# connector.net
KiCad netlist of a schematic drawn in Altium Designer
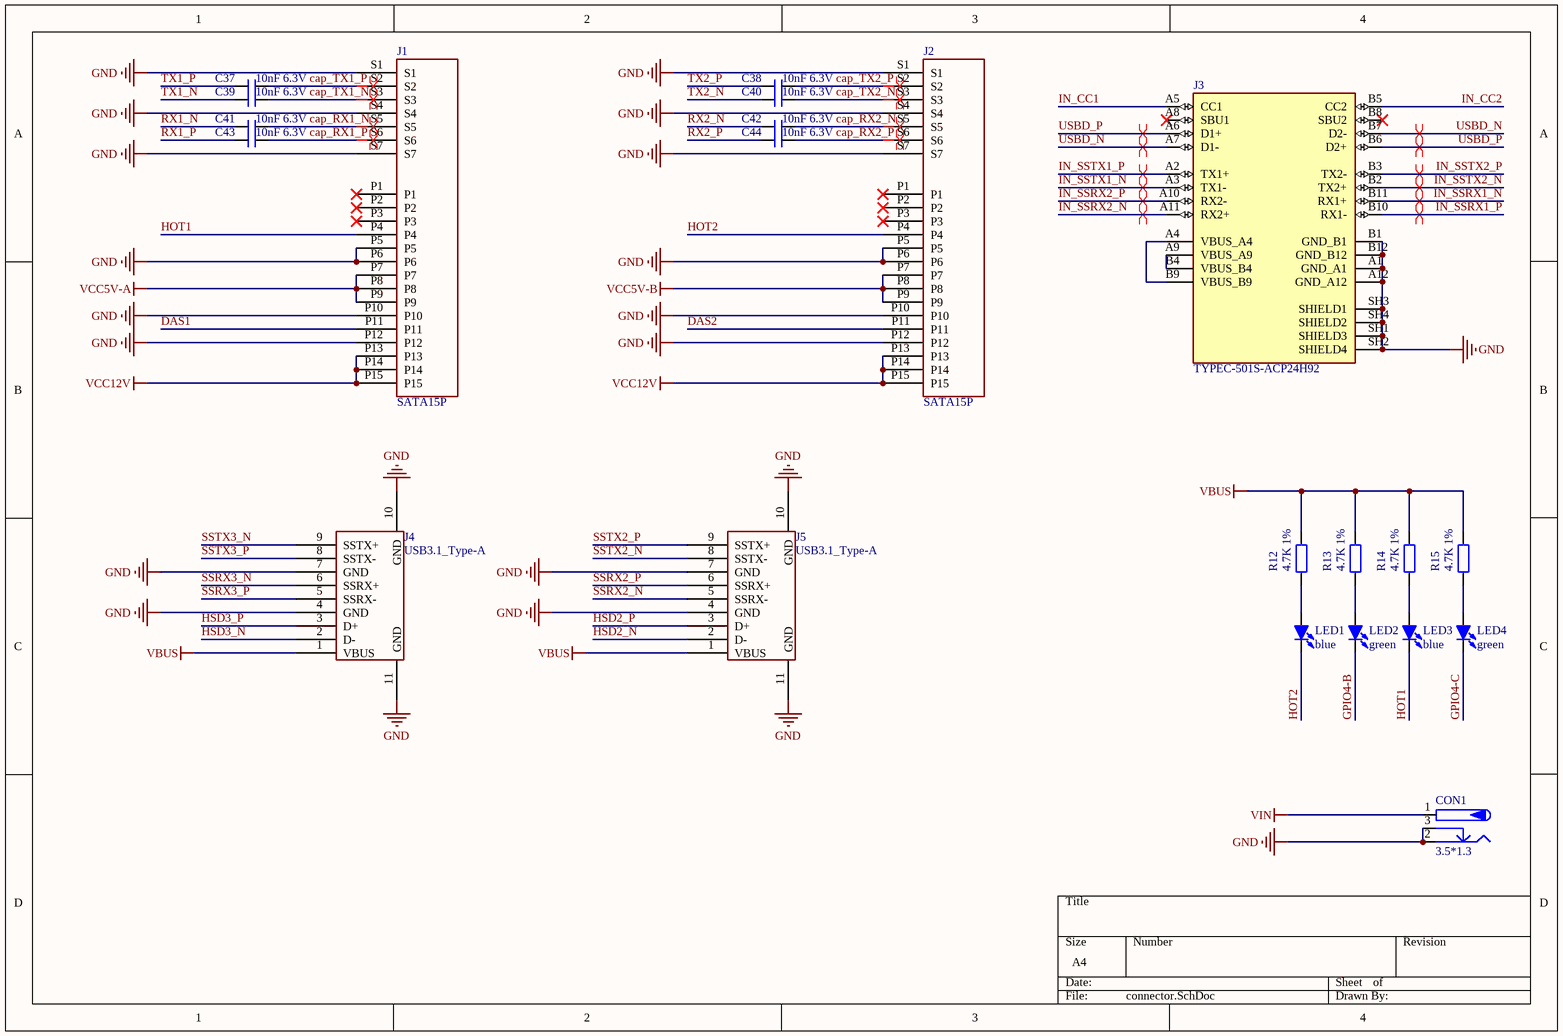
[diagram p0: connector.SchDoc]

(export (version "E")
  (design (tool "Eeschema 10.0.6"))
  (components
    (comp (ref "C37")
      (value "10nF 6.3V")
      (footprint "C0402_L")
      (description "无极性贴片电容")
      (fields (field (name "版权归属") "源创客"))
      (libsource (lib "Capacitor") (part "C"))
    )
    (comp (ref "C38")
      (value "10nF 6.3V")
      (footprint "C0402_L")
      (description "无极性贴片电容")
      (fields (field (name "版权归属") "源创客"))
      (libsource (lib "Capacitor") (part "C"))
    )
    (comp (ref "C39")
      (value "10nF 6.3V")
      (footprint "C0402_L")
      (description "无极性贴片电容")
      (fields (field (name "版权归属") "源创客"))
      (libsource (lib "Capacitor") (part "C"))
    )
    (comp (ref "C40")
      (value "10nF 6.3V")
      (footprint "C0402_L")
      (description "无极性贴片电容")
      (fields (field (name "版权归属") "源创客"))
      (libsource (lib "Capacitor") (part "C"))
    )
    (comp (ref "C41")
      (value "10nF 6.3V")
      (footprint "C0402_L")
      (description "无极性贴片电容")
      (fields (field (name "版权归属") "源创客"))
      (libsource (lib "Capacitor") (part "C"))
    )
    (comp (ref "C42")
      (value "10nF 6.3V")
      (footprint "C0402_L")
      (description "无极性贴片电容")
      (fields (field (name "版权归属") "源创客"))
      (libsource (lib "Capacitor") (part "C"))
    )
    (comp (ref "C43")
      (value "10nF 6.3V")
      (footprint "C0402_L")
      (description "无极性贴片电容")
      (fields (field (name "版权归属") "源创客"))
      (libsource (lib "Capacitor") (part "C"))
    )
    (comp (ref "C44")
      (value "10nF 6.3V")
      (footprint "C0402_L")
      (description "无极性贴片电容")
      (fields (field (name "版权归属") "源创客"))
      (libsource (lib "Capacitor") (part "C"))
    )
    (comp (ref "CON1")
      (value "3.5*1.3")
      (footprint "DC-012G-2.5")
      (description "低压电源接口")
      (fields (field (name "版权归属") "源创客"))
      (libsource (lib "Connector-PWR") (part "P-DC"))
    )
    (comp (ref "J1")
      (value "SATA15P")
      (footprint "SATA 15P 贴片")
      (libsource (lib "Connector-SATA&SAS") (part "SATA15P"))
    )
    (comp (ref "J2")
      (value "SATA15P")
      (footprint "SATA 15P 贴片")
      (libsource (lib "Connector-SATA&SAS") (part "SATA15P"))
    )
    (comp (ref "J3")
      (value "TYPEC-501S-ACP24H92")
      (footprint "TypeC 24p 直立")
      (fields (field (name "MF") "Molex") (field (name "MP") "1054500101"))
      (libsource (lib "Connector-USB") (part "Typec 24p"))
    )
    (comp (ref "J4")
      (value "USB3.1_Type-A")
      (footprint "USB3.1_Type-A 立式直插")
      (description "USB接口")
      (libsource (lib "Connector-USB") (part "USB3.1_Type-A"))
    )
    (comp (ref "J5")
      (value "USB3.1_Type-A")
      (footprint "USB3.1_Type-A 立式直插")
      (description "USB接口")
      (libsource (lib "Connector-USB") (part "USB3.1_Type-A"))
    )
    (comp (ref "LED1")
      (value "blue")
      (footprint "LED 0805B")
      (description "插件LED")
      (fields (field (name "版权归属") "源创客"))
      (libsource (lib "LED") (part "LED-3MM"))
    )
    (comp (ref "LED2")
      (value "green")
      (footprint "LED 0805G")
      (description "插件LED")
      (fields (field (name "版权归属") "源创客"))
      (libsource (lib "LED") (part "LED-3MM"))
    )
    (comp (ref "LED3")
      (value "blue")
      (footprint "LED 0805B")
      (description "插件LED")
      (fields (field (name "版权归属") "源创客"))
      (libsource (lib "LED") (part "LED-3MM"))
    )
    (comp (ref "LED4")
      (value "green")
      (footprint "LED 0805G")
      (description "插件LED")
      (fields (field (name "版权归属") "源创客"))
      (libsource (lib "LED") (part "LED-3MM"))
    )
    (comp (ref "R12")
      (value "4.7K 1%")
      (footprint "R0402_L")
      (description "贴片电阻")
      (fields (field (name "版权归属") "源创客"))
      (libsource (lib "Resistor") (part "R"))
    )
    (comp (ref "R13")
      (value "4.7K 1%")
      (footprint "R0402_L")
      (description "贴片电阻")
      (fields (field (name "版权归属") "源创客"))
      (libsource (lib "Resistor") (part "R"))
    )
    (comp (ref "R14")
      (value "4.7K 1%")
      (footprint "R0402_L")
      (description "贴片电阻")
      (fields (field (name "版权归属") "源创客"))
      (libsource (lib "Resistor") (part "R"))
    )
    (comp (ref "R15")
      (value "4.7K 1%")
      (footprint "R0402_L")
      (description "贴片电阻")
      (fields (field (name "版权归属") "源创客"))
      (libsource (lib "Resistor") (part "R"))
    )
  )
  (nets
    (net (code "1") (name "/DAS1") (class "Default")
      (node (ref "J1") (pin "P11") (pinfunction "P11_P11") (pintype "passive"))
    )
    (net (code "2") (name "/DAS2") (class "Default")
      (node (ref "J2") (pin "P11") (pinfunction "P11_P11") (pintype "passive"))
    )
    (net (code "3") (name "/GPIO4-B") (class "Default")
      (node (ref "LED2") (pin "2") (pinfunction "K_2") (pintype "passive"))
    )
    (net (code "4") (name "/GPIO4-C") (class "Default")
      (node (ref "LED4") (pin "2") (pinfunction "K_2") (pintype "passive"))
    )
    (net (code "5") (name "/HOT1") (class "Default")
      (node (ref "J1") (pin "P4") (pinfunction "P4_P4") (pintype "passive"))
      (node (ref "LED3") (pin "2") (pinfunction "K_2") (pintype "passive"))
    )
    (net (code "6") (name "/HOT2") (class "Default")
      (node (ref "J2") (pin "P4") (pinfunction "P4_P4") (pintype "passive"))
      (node (ref "LED1") (pin "2") (pinfunction "K_2") (pintype "passive"))
    )
    (net (code "7") (name "/HSD2_N") (class "Default")
      (node (ref "J5") (pin "2") (pinfunction "D-_2") (pintype "passive"))
    )
    (net (code "8") (name "/HSD2_P") (class "Default")
      (node (ref "J5") (pin "3") (pinfunction "D+_3") (pintype "passive"))
    )
    (net (code "9") (name "/HSD3_N") (class "Default")
      (node (ref "J4") (pin "2") (pinfunction "D-_2") (pintype "passive"))
    )
    (net (code "10") (name "/HSD3_P") (class "Default")
      (node (ref "J4") (pin "3") (pinfunction "D+_3") (pintype "passive"))
    )
    (net (code "11") (name "/IN_CC1") (class "Default")
      (node (ref "J3") (pin "A5") (pinfunction "CC1_A5") (pintype "bidirectional"))
    )
    (net (code "12") (name "/IN_CC2") (class "Default")
      (node (ref "J3") (pin "B5") (pinfunction "CC2_B5") (pintype "bidirectional"))
    )
    (net (code "13") (name "/IN_SSRX1_N") (class "Default")
      (node (ref "J3") (pin "B11") (pinfunction "RX1+_B11") (pintype "bidirectional"))
    )
    (net (code "14") (name "/IN_SSRX1_P") (class "Default")
      (node (ref "J3") (pin "B10") (pinfunction "RX1-_B10") (pintype "bidirectional"))
    )
    (net (code "15") (name "/IN_SSRX2_N") (class "Default")
      (node (ref "J3") (pin "A11") (pinfunction "RX2+_A11") (pintype "bidirectional"))
    )
    (net (code "16") (name "/IN_SSRX2_P") (class "Default")
      (node (ref "J3") (pin "A10") (pinfunction "RX2-_A10") (pintype "bidirectional"))
    )
    (net (code "17") (name "/IN_SSTX1_N") (class "Default")
      (node (ref "J3") (pin "A3") (pinfunction "TX1-_A3") (pintype "bidirectional"))
    )
    (net (code "18") (name "/IN_SSTX1_P") (class "Default")
      (node (ref "J3") (pin "A2") (pinfunction "TX1+_A2") (pintype "bidirectional"))
    )
    (net (code "19") (name "/IN_SSTX2_N") (class "Default")
      (node (ref "J3") (pin "B2") (pinfunction "TX2+_B2") (pintype "bidirectional"))
    )
    (net (code "20") (name "/IN_SSTX2_P") (class "Default")
      (node (ref "J3") (pin "B3") (pinfunction "TX2-_B3") (pintype "bidirectional"))
    )
    (net (code "21") (name "/RX1_N") (class "Default")
      (node (ref "C41") (pin "2") (pinfunction "2_2") (pintype "passive"))
    )
    (net (code "22") (name "/RX1_P") (class "Default")
      (node (ref "C43") (pin "2") (pinfunction "2_2") (pintype "passive"))
    )
    (net (code "23") (name "/RX2_N") (class "Default")
      (node (ref "C42") (pin "2") (pinfunction "2_2") (pintype "passive"))
    )
    (net (code "24") (name "/RX2_P") (class "Default")
      (node (ref "C44") (pin "2") (pinfunction "2_2") (pintype "passive"))
    )
    (net (code "25") (name "/SSRX2_N") (class "Default")
      (node (ref "J5") (pin "5") (pinfunction "SSRX-_5") (pintype "passive"))
    )
    (net (code "26") (name "/SSRX2_P") (class "Default")
      (node (ref "J5") (pin "6") (pinfunction "SSRX+_6") (pintype "passive"))
    )
    (net (code "27") (name "/SSRX3_N") (class "Default")
      (node (ref "J4") (pin "6") (pinfunction "SSRX+_6") (pintype "passive"))
    )
    (net (code "28") (name "/SSRX3_P") (class "Default")
      (node (ref "J4") (pin "5") (pinfunction "SSRX-_5") (pintype "passive"))
    )
    (net (code "29") (name "/SSTX2_N") (class "Default")
      (node (ref "J5") (pin "8") (pinfunction "SSTX-_8") (pintype "passive"))
    )
    (net (code "30") (name "/SSTX2_P") (class "Default")
      (node (ref "J5") (pin "9") (pinfunction "SSTX+_9") (pintype "passive"))
    )
    (net (code "31") (name "/SSTX3_N") (class "Default")
      (node (ref "J4") (pin "9") (pinfunction "SSTX+_9") (pintype "passive"))
    )
    (net (code "32") (name "/SSTX3_P") (class "Default")
      (node (ref "J4") (pin "8") (pinfunction "SSTX-_8") (pintype "passive"))
    )
    (net (code "33") (name "/TX1_N") (class "Default")
      (node (ref "C39") (pin "2") (pinfunction "2_2") (pintype "passive"))
    )
    (net (code "34") (name "/TX1_P") (class "Default")
      (node (ref "C37") (pin "2") (pinfunction "2_2") (pintype "passive"))
    )
    (net (code "35") (name "/TX2_N") (class "Default")
      (node (ref "C40") (pin "2") (pinfunction "2_2") (pintype "passive"))
    )
    (net (code "36") (name "/TX2_P") (class "Default")
      (node (ref "C38") (pin "2") (pinfunction "2_2") (pintype "passive"))
    )
    (net (code "37") (name "/USBD_N") (class "Default")
      (node (ref "J3") (pin "A7") (pinfunction "D1-_A7") (pintype "bidirectional"))
      (node (ref "J3") (pin "B7") (pinfunction "D2-_B7") (pintype "bidirectional"))
    )
    (net (code "38") (name "/USBD_P") (class "Default")
      (node (ref "J3") (pin "A6") (pinfunction "D1+_A6") (pintype "bidirectional"))
      (node (ref "J3") (pin "B6") (pinfunction "D2+_B6") (pintype "bidirectional"))
    )
    (net (code "39") (name "/cap_RX1_N") (class "Default")
      (node (ref "C41") (pin "1") (pinfunction "1_1") (pintype "passive"))
      (node (ref "J1") (pin "S5") (pinfunction "S5_S5") (pintype "passive"))
    )
    (net (code "40") (name "/cap_RX1_P") (class "Default")
      (node (ref "C43") (pin "1") (pinfunction "1_1") (pintype "passive"))
      (node (ref "J1") (pin "S6") (pinfunction "S6_S6") (pintype "passive"))
    )
    (net (code "41") (name "/cap_RX2_N") (class "Default")
      (node (ref "C42") (pin "1") (pinfunction "1_1") (pintype "passive"))
      (node (ref "J2") (pin "S5") (pinfunction "S5_S5") (pintype "passive"))
    )
    (net (code "42") (name "/cap_RX2_P") (class "Default")
      (node (ref "C44") (pin "1") (pinfunction "1_1") (pintype "passive"))
      (node (ref "J2") (pin "S6") (pinfunction "S6_S6") (pintype "passive"))
    )
    (net (code "43") (name "/cap_TX1_N") (class "Default")
      (node (ref "C39") (pin "1") (pinfunction "1_1") (pintype "passive"))
      (node (ref "J1") (pin "S3") (pinfunction "S3_S3") (pintype "passive"))
    )
    (net (code "44") (name "/cap_TX1_P") (class "Default")
      (node (ref "C37") (pin "1") (pinfunction "1_1") (pintype "passive"))
      (node (ref "J1") (pin "S2") (pinfunction "S2_S2") (pintype "passive"))
    )
    (net (code "45") (name "/cap_TX2_N") (class "Default")
      (node (ref "C40") (pin "1") (pinfunction "1_1") (pintype "passive"))
      (node (ref "J2") (pin "S3") (pinfunction "S3_S3") (pintype "passive"))
    )
    (net (code "46") (name "/cap_TX2_P") (class "Default")
      (node (ref "C38") (pin "1") (pinfunction "1_1") (pintype "passive"))
      (node (ref "J2") (pin "S2") (pinfunction "S2_S2") (pintype "passive"))
    )
    (net (code "47") (name "GND") (class "Default")
      (node (ref "CON1") (pin "2") (pintype "power_in"))
      (node (ref "CON1") (pin "3") (pintype "power_in"))
      (node (ref "J1") (pin "P10") (pinfunction "P10_P10") (pintype "passive"))
      (node (ref "J1") (pin "P12") (pinfunction "P12_P12") (pintype "passive"))
      (node (ref "J1") (pin "P5") (pinfunction "P5_P5") (pintype "passive"))
      (node (ref "J1") (pin "P6") (pinfunction "P6_P6") (pintype "passive"))
      (node (ref "J1") (pin "S1") (pinfunction "S1_S1") (pintype "passive"))
      (node (ref "J1") (pin "S4") (pinfunction "S4_S4") (pintype "passive"))
      (node (ref "J1") (pin "S7") (pinfunction "S7_S7") (pintype "passive"))
      (node (ref "J2") (pin "P10") (pinfunction "P10_P10") (pintype "passive"))
      (node (ref "J2") (pin "P12") (pinfunction "P12_P12") (pintype "passive"))
      (node (ref "J2") (pin "P5") (pinfunction "P5_P5") (pintype "passive"))
      (node (ref "J2") (pin "P6") (pinfunction "P6_P6") (pintype "passive"))
      (node (ref "J2") (pin "S1") (pinfunction "S1_S1") (pintype "passive"))
      (node (ref "J2") (pin "S4") (pinfunction "S4_S4") (pintype "passive"))
      (node (ref "J2") (pin "S7") (pinfunction "S7_S7") (pintype "passive"))
      (node (ref "J3") (pin "A1") (pinfunction "GND_A1_A1") (pintype "power_in"))
      (node (ref "J3") (pin "A12") (pinfunction "GND_A12_A12") (pintype "power_in"))
      (node (ref "J3") (pin "B1") (pinfunction "GND_B1_B1") (pintype "power_in"))
      (node (ref "J3") (pin "B12") (pinfunction "GND_B12_B12") (pintype "power_in"))
      (node (ref "J3") (pin "SH1") (pinfunction "SHIELD3_SH1") (pintype "passive"))
      (node (ref "J3") (pin "SH2") (pinfunction "SHIELD4_SH2") (pintype "passive"))
      (node (ref "J3") (pin "SH3") (pinfunction "SHIELD1_SH3") (pintype "passive"))
      (node (ref "J3") (pin "SH4") (pinfunction "SHIELD2_SH4") (pintype "passive"))
      (node (ref "J4") (pin "10") (pinfunction "GND_10") (pintype "passive"))
      (node (ref "J4") (pin "11") (pinfunction "GND_11") (pintype "passive"))
      (node (ref "J4") (pin "4") (pinfunction "GND_4") (pintype "passive"))
      (node (ref "J4") (pin "7") (pinfunction "GND_7") (pintype "passive"))
      (node (ref "J5") (pin "10") (pinfunction "GND_10") (pintype "passive"))
      (node (ref "J5") (pin "11") (pinfunction "GND_11") (pintype "passive"))
      (node (ref "J5") (pin "4") (pinfunction "GND_4") (pintype "passive"))
      (node (ref "J5") (pin "7") (pinfunction "GND_7") (pintype "passive"))
    )
    (net (code "48") (name "Net-(J3-VBUS_A4)") (class "Default")
      (node (ref "J3") (pin "A4") (pinfunction "VBUS_A4_A4") (pintype "power_in"))
      (node (ref "J3") (pin "B9") (pinfunction "VBUS_B9_B9") (pintype "power_in"))
    )
    (net (code "49") (name "Net-(J3-VBUS_A9)") (class "Default")
      (node (ref "J3") (pin "A9") (pinfunction "VBUS_A9_A9") (pintype "power_in"))
      (node (ref "J3") (pin "B4") (pinfunction "VBUS_B4_B4") (pintype "power_in"))
    )
    (net (code "50") (name "Net-(LED1-A)") (class "Default")
      (node (ref "LED1") (pin "1") (pinfunction "A_1") (pintype "passive"))
      (node (ref "R12") (pin "2") (pinfunction "2_2") (pintype "passive"))
    )
    (net (code "51") (name "Net-(LED2-A)") (class "Default")
      (node (ref "LED2") (pin "1") (pinfunction "A_1") (pintype "passive"))
      (node (ref "R13") (pin "2") (pinfunction "2_2") (pintype "passive"))
    )
    (net (code "52") (name "Net-(LED3-A)") (class "Default")
      (node (ref "LED3") (pin "1") (pinfunction "A_1") (pintype "passive"))
      (node (ref "R14") (pin "2") (pinfunction "2_2") (pintype "passive"))
    )
    (net (code "53") (name "Net-(LED4-A)") (class "Default")
      (node (ref "LED4") (pin "1") (pinfunction "A_1") (pintype "passive"))
      (node (ref "R15") (pin "2") (pinfunction "2_2") (pintype "passive"))
    )
    (net (code "54") (name "VBUS") (class "Default")
      (node (ref "J4") (pin "1") (pinfunction "VBUS_1") (pintype "passive"))
      (node (ref "J5") (pin "1") (pinfunction "VBUS_1") (pintype "passive"))
      (node (ref "R12") (pin "1") (pinfunction "1_1") (pintype "passive"))
      (node (ref "R13") (pin "1") (pinfunction "1_1") (pintype "passive"))
      (node (ref "R14") (pin "1") (pinfunction "1_1") (pintype "passive"))
      (node (ref "R15") (pin "1") (pinfunction "1_1") (pintype "passive"))
    )
    (net (code "55") (name "VCC5V-A") (class "Default")
      (node (ref "J1") (pin "P7") (pinfunction "P7_P7") (pintype "passive"))
      (node (ref "J1") (pin "P8") (pinfunction "P8_P8") (pintype "passive"))
      (node (ref "J1") (pin "P9") (pinfunction "P9_P9") (pintype "passive"))
    )
    (net (code "56") (name "VCC5V-B") (class "Default")
      (node (ref "J2") (pin "P7") (pinfunction "P7_P7") (pintype "passive"))
      (node (ref "J2") (pin "P8") (pinfunction "P8_P8") (pintype "passive"))
      (node (ref "J2") (pin "P9") (pinfunction "P9_P9") (pintype "passive"))
    )
    (net (code "57") (name "VCC12V") (class "Default")
      (node (ref "J1") (pin "P13") (pinfunction "P13_P13") (pintype "passive"))
      (node (ref "J1") (pin "P14") (pinfunction "P14_P14") (pintype "passive"))
      (node (ref "J1") (pin "P15") (pinfunction "P15_P15") (pintype "passive"))
      (node (ref "J2") (pin "P13") (pinfunction "P13_P13") (pintype "passive"))
      (node (ref "J2") (pin "P14") (pinfunction "P14_P14") (pintype "passive"))
      (node (ref "J2") (pin "P15") (pinfunction "P15_P15") (pintype "passive"))
    )
    (net (code "58") (name "VIN") (class "Default") (node (ref "CON1") (pin "1") (pintype "power_in")))
    (net (code "59") (name "unconnected-(J1-PadP1)") (class "Default")
      (node (ref "J1") (pin "P1") (pinfunction "P1_P1") (pintype "passive+no_connect"))
    )
    (net (code "60") (name "unconnected-(J1-PadP2)") (class "Default")
      (node (ref "J1") (pin "P2") (pinfunction "P2_P2") (pintype "passive+no_connect"))
    )
    (net (code "61") (name "unconnected-(J1-PadP3)") (class "Default")
      (node (ref "J1") (pin "P3") (pinfunction "P3_P3") (pintype "passive+no_connect"))
    )
    (net (code "62") (name "unconnected-(J2-PadP1)") (class "Default")
      (node (ref "J2") (pin "P1") (pinfunction "P1_P1") (pintype "passive+no_connect"))
    )
    (net (code "63") (name "unconnected-(J2-PadP2)") (class "Default")
      (node (ref "J2") (pin "P2") (pinfunction "P2_P2") (pintype "passive+no_connect"))
    )
    (net (code "64") (name "unconnected-(J2-PadP3)") (class "Default")
      (node (ref "J2") (pin "P3") (pinfunction "P3_P3") (pintype "passive+no_connect"))
    )
    (net (code "65") (name "unconnected-(J3-SBU1-PadA8)") (class "Default")
      (node (ref "J3") (pin "A8") (pinfunction "SBU1_A8") (pintype "bidirectional+no_connect"))
    )
    (net (code "66") (name "unconnected-(J3-SBU2-PadB8)") (class "Default")
      (node (ref "J3") (pin "B8") (pinfunction "SBU2_B8") (pintype "bidirectional+no_connect"))
    )
  )
)
